# Arduino-Pro-Mini.net
KiCad netlist of a schematic drawn in EAGLE
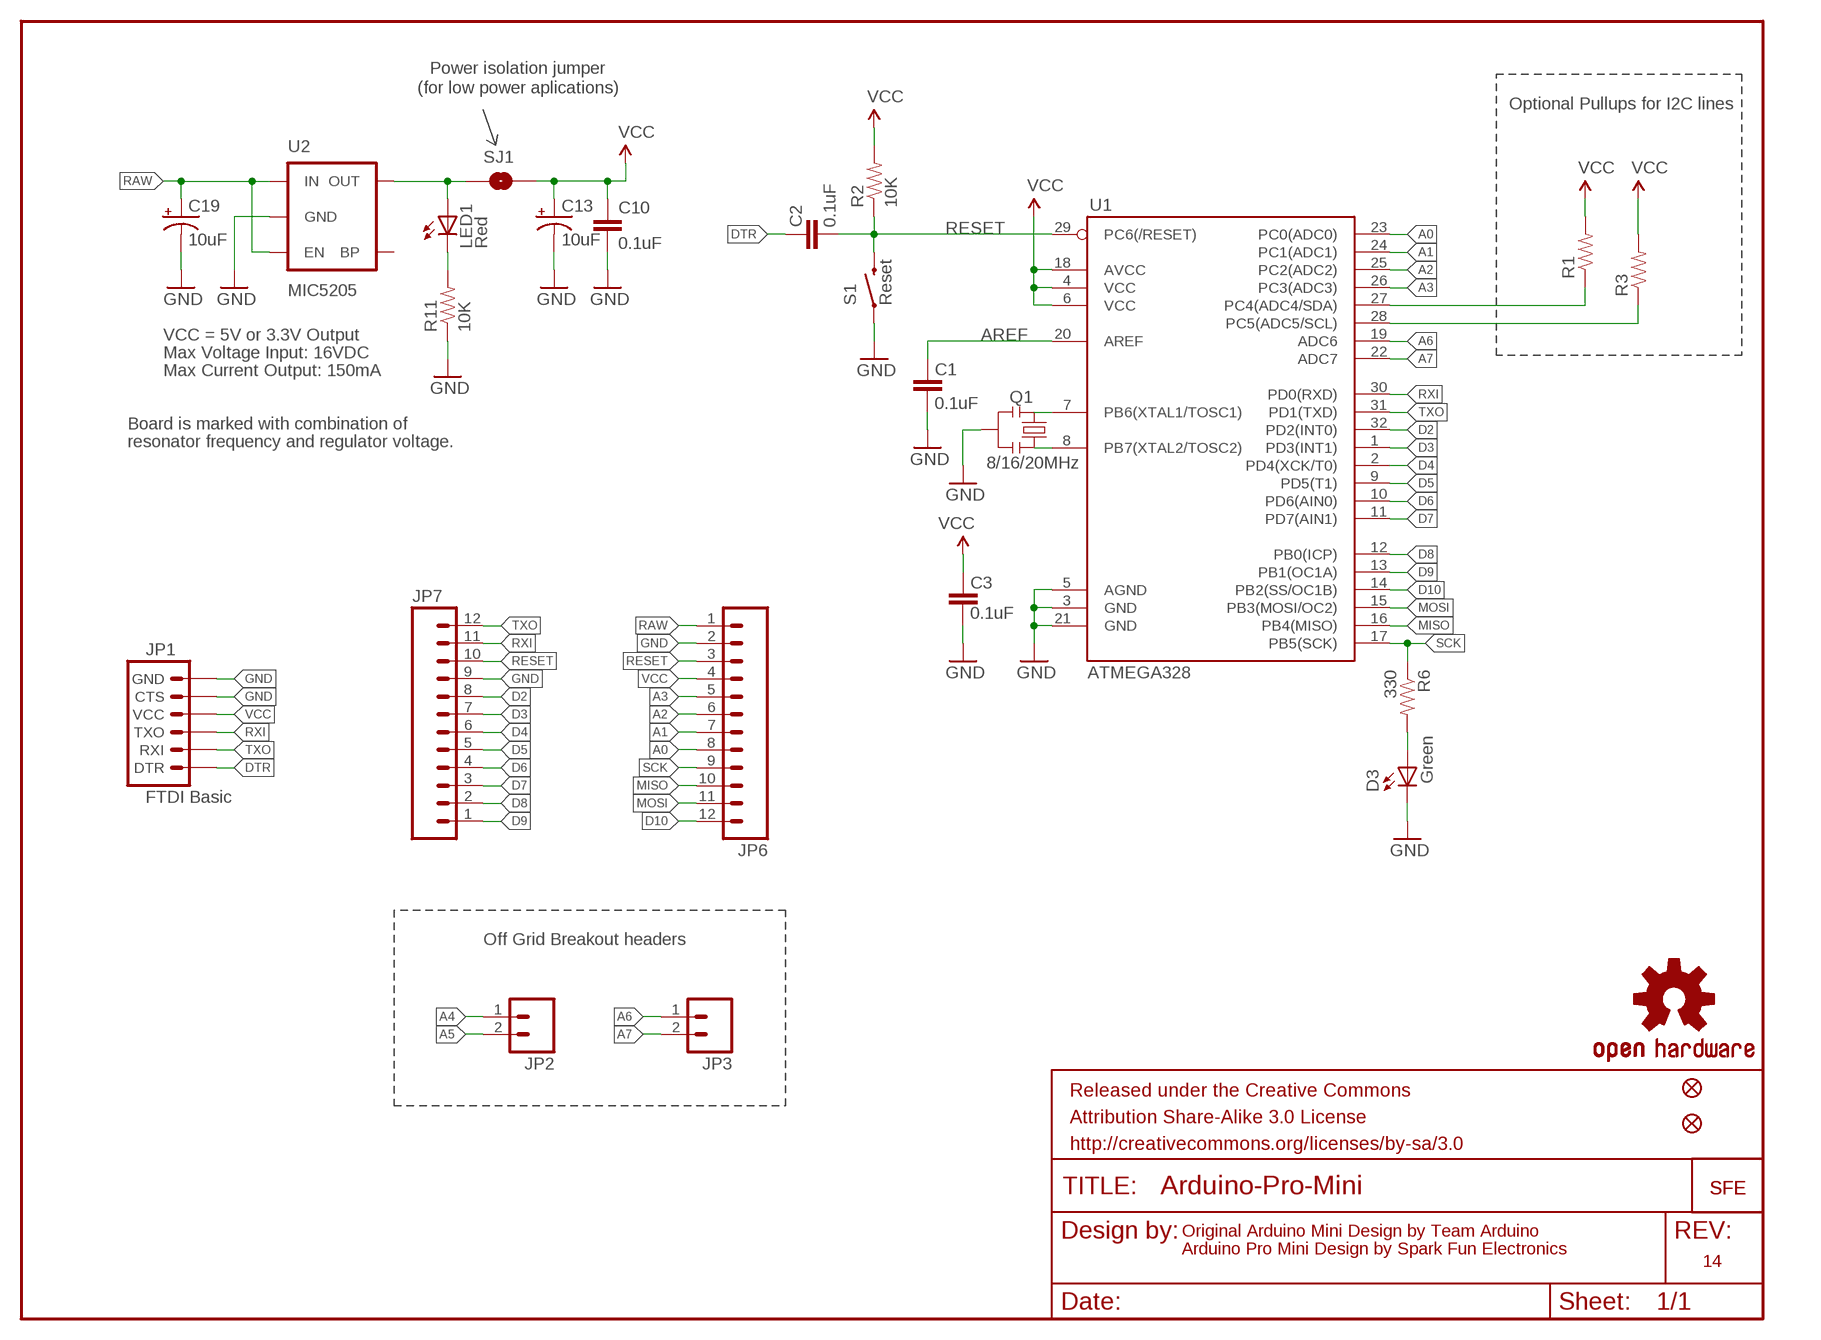
[diagram p0: schematic, sheet 1]

(export (version "E")
  (design (tool "Eeschema 10.0.6"))
  (components
    (comp (ref "C1")
      (value "0.1uF")
      (footprint "eagle-import:0603-CAP")
      (libsource (lib "eagle-import") (part "CAP0603-CAP"))
    )
    (comp (ref "C2")
      (value "0.1uF")
      (footprint "eagle-import:0603-CAP")
      (libsource (lib "eagle-import") (part "CAP0603-CAP"))
    )
    (comp (ref "C3")
      (value "0.1uF")
      (footprint "eagle-import:0603-CAP")
      (libsource (lib "eagle-import") (part "CAP0603-CAP"))
    )
    (comp (ref "C10")
      (value "0.1uF")
      (footprint "eagle-import:0603-CAP")
      (libsource (lib "eagle-import") (part "CAP0603-CAP"))
    )
    (comp (ref "C13")
      (value "10uF")
      (footprint "eagle-import:EIA3216")
      (libsource (lib "eagle-import") (part "CAP_POL1206"))
    )
    (comp (ref "C19")
      (value "10uF")
      (footprint "eagle-import:EIA3216")
      (libsource (lib "eagle-import") (part "CAP_POL1206"))
    )
    (comp (ref "D3")
      (value "Green")
      (footprint "eagle-import:LED-0603")
      (libsource (lib "eagle-import") (part "LED0603"))
    )
    (comp (ref "FRAME1")
      (value "FRAME-LETTER")
      (footprint "eagle-import:CREATIVE_COMMONS")
      (libsource (lib "eagle-import") (part "FRAME-LETTER"))
    )
    (comp (ref "JP1")
      (value "FTDI Basic")
      (footprint "eagle-import:1X06")
      (libsource (lib "eagle-import") (part "ARDUINO_SERIAL_PROGRAMPTH"))
    )
    (comp (ref "JP2")
      (value "M02PTH")
      (footprint "eagle-import:1X02")
      (libsource (lib "eagle-import") (part "M02PTH"))
    )
    (comp (ref "JP3")
      (value "M02PTH")
      (footprint "eagle-import:1X02")
      (libsource (lib "eagle-import") (part "M02PTH"))
    )
    (comp (ref "JP5")
      (value "FIDUCIALUFIDUCIAL")
      (footprint "eagle-import:MICRO-FIDUCIAL")
      (libsource (lib "eagle-import") (part "FIDUCIALUFIDUCIAL"))
    )
    (comp (ref "JP6")
      (value "M12PTH")
      (footprint "eagle-import:1X12")
      (libsource (lib "eagle-import") (part "M12PTH"))
    )
    (comp (ref "JP7")
      (value "M12PTH")
      (footprint "eagle-import:1X12")
      (libsource (lib "eagle-import") (part "M12PTH"))
    )
    (comp (ref "JP8")
      (value "FIDUCIALUFIDUCIAL")
      (footprint "eagle-import:MICRO-FIDUCIAL")
      (libsource (lib "eagle-import") (part "FIDUCIALUFIDUCIAL"))
    )
    (comp (ref "LED1")
      (value "Red")
      (footprint "eagle-import:LED-0603")
      (libsource (lib "eagle-import") (part "LED0603"))
    )
    (comp (ref "Q1")
      (value "8/16/20MHz")
      (footprint "eagle-import:RESONATOR-SMD-1_1")
      (libsource (lib "eagle-import") (part "RESONATOR1{colon}1"))
    )
    (comp (ref "R1")
      (value "RESISTOR0603-RES")
      (footprint "eagle-import:0603-RES")
      (libsource (lib "eagle-import") (part "RESISTOR0603-RES"))
    )
    (comp (ref "R2")
      (value "10K")
      (footprint "eagle-import:0603-RES")
      (libsource (lib "eagle-import") (part "RESISTOR0603-RES"))
    )
    (comp (ref "R3")
      (value "RESISTOR0603-RES")
      (footprint "eagle-import:0603-RES")
      (libsource (lib "eagle-import") (part "RESISTOR0603-RES"))
    )
    (comp (ref "R6")
      (value "330")
      (footprint "eagle-import:0603-RES")
      (libsource (lib "eagle-import") (part "RESISTOR0603-RES"))
    )
    (comp (ref "R11")
      (value "10K")
      (footprint "eagle-import:0603-RES")
      (libsource (lib "eagle-import") (part "RESISTOR0603-RES"))
    )
    (comp (ref "S1")
      (value "Reset")
      (footprint "eagle-import:TACTILE-SWITCH-SMD-ALT01")
      (libsource (lib "eagle-import") (part "SWITCH-MOMENTARY-2SMD-ALT01"))
    )
    (comp (ref "SJ1")
      (value "SOLDERJUMPERNC")
      (footprint "eagle-import:SJ_2S")
      (libsource (lib "eagle-import") (part "SOLDERJUMPERNC"))
    )
    (comp (ref "U$1")
      (value "LOGO-SFESK")
      (footprint "eagle-import:SFE-LOGO-FLAME")
      (libsource (lib "eagle-import") (part "LOGO-SFESK"))
    )
    (comp (ref "U$3")
      (value "OSHW-LOGOS")
      (footprint "eagle-import:OSHW-LOGO-S")
      (libsource (lib "eagle-import") (part "OSHW-LOGOS"))
    )
    (comp (ref "U$11")
      (value "LOGO-SFENEW")
      (footprint "eagle-import:SFE-NEW-WEBLOGO")
      (libsource (lib "eagle-import") (part "LOGO-SFENEW"))
    )
    (comp (ref "U1")
      (value "ATMEGA328")
      (footprint "eagle-import:TQFP32-08")
      (libsource (lib "eagle-import") (part "ATMEGA168"))
    )
    (comp (ref "U2")
      (value "MIC5205")
      (footprint "eagle-import:SOT23-5")
      (libsource (lib "eagle-import") (part "V_REG_LDOSMD"))
    )
  )
  (nets
    (net (code "1") (name "/AREF") (class "Default")
      (node (ref "C1") (pin "2") (pinfunction "2_2") (pintype "passive"))
      (node (ref "U1") (pin "20") (pinfunction "AREF_20") (pintype "bidirectional"))
    )
    (net (code "2") (name "A0") (class "Default")
      (node (ref "JP6") (pin "8") (pinfunction "8_8") (pintype "passive"))
      (node (ref "U1") (pin "23") (pinfunction "PC0(ADC0)_23") (pintype "bidirectional"))
    )
    (net (code "3") (name "A1") (class "Default")
      (node (ref "JP6") (pin "7") (pinfunction "7_7") (pintype "passive"))
      (node (ref "U1") (pin "24") (pinfunction "PC1(ADC1)_24") (pintype "bidirectional"))
    )
    (net (code "4") (name "A2") (class "Default")
      (node (ref "JP6") (pin "6") (pinfunction "6_6") (pintype "passive"))
      (node (ref "U1") (pin "25") (pinfunction "PC2(ADC2)_25") (pintype "bidirectional"))
    )
    (net (code "5") (name "A3") (class "Default")
      (node (ref "JP6") (pin "5") (pinfunction "5_5") (pintype "passive"))
      (node (ref "U1") (pin "26") (pinfunction "PC3(ADC3)_26") (pintype "bidirectional"))
    )
    (net (code "6") (name "A4") (class "Default")
      (node (ref "JP2") (pin "1") (pinfunction "1_1") (pintype "passive"))
      (node (ref "R1") (pin "1") (pinfunction "1_1") (pintype "passive"))
      (node (ref "U1") (pin "27") (pinfunction "PC4(ADC4/SDA)_27") (pintype "bidirectional"))
    )
    (net (code "7") (name "A5") (class "Default")
      (node (ref "JP2") (pin "2") (pinfunction "2_2") (pintype "passive"))
      (node (ref "R3") (pin "1") (pinfunction "1_1") (pintype "passive"))
      (node (ref "U1") (pin "28") (pinfunction "PC5(ADC5/SCL)_28") (pintype "bidirectional"))
    )
    (net (code "8") (name "A6") (class "Default")
      (node (ref "JP3") (pin "1") (pinfunction "1_1") (pintype "passive"))
      (node (ref "U1") (pin "19") (pinfunction "ADC6_19") (pintype "bidirectional"))
    )
    (net (code "9") (name "A7") (class "Default")
      (node (ref "JP3") (pin "2") (pinfunction "2_2") (pintype "passive"))
      (node (ref "U1") (pin "22") (pinfunction "ADC7_22") (pintype "bidirectional"))
    )
    (net (code "10") (name "D2") (class "Default")
      (node (ref "JP7") (pin "8") (pinfunction "8_8") (pintype "passive"))
      (node (ref "U1") (pin "32") (pinfunction "PD2(INT0)_32") (pintype "bidirectional"))
    )
    (net (code "11") (name "D3") (class "Default")
      (node (ref "JP7") (pin "7") (pinfunction "7_7") (pintype "passive"))
      (node (ref "U1") (pin "1") (pinfunction "PD3(INT1)_1") (pintype "bidirectional"))
    )
    (net (code "12") (name "D4") (class "Default")
      (node (ref "JP7") (pin "6") (pinfunction "6_6") (pintype "passive"))
      (node (ref "U1") (pin "2") (pinfunction "PD4(XCK/T0)_2") (pintype "bidirectional"))
    )
    (net (code "13") (name "D5") (class "Default")
      (node (ref "JP7") (pin "5") (pinfunction "5_5") (pintype "passive"))
      (node (ref "U1") (pin "9") (pinfunction "PD5(T1)_9") (pintype "bidirectional"))
    )
    (net (code "14") (name "D6") (class "Default")
      (node (ref "JP7") (pin "4") (pinfunction "4_4") (pintype "passive"))
      (node (ref "U1") (pin "10") (pinfunction "PD6(AIN0)_10") (pintype "bidirectional"))
    )
    (net (code "15") (name "D7") (class "Default")
      (node (ref "JP7") (pin "3") (pinfunction "3_3") (pintype "passive"))
      (node (ref "U1") (pin "11") (pinfunction "PD7(AIN1)_11") (pintype "bidirectional"))
    )
    (net (code "16") (name "D8") (class "Default")
      (node (ref "JP7") (pin "2") (pinfunction "2_2") (pintype "passive"))
      (node (ref "U1") (pin "12") (pinfunction "PB0(ICP)_12") (pintype "bidirectional"))
    )
    (net (code "17") (name "D9") (class "Default")
      (node (ref "JP7") (pin "1") (pinfunction "1_1") (pintype "passive"))
      (node (ref "U1") (pin "13") (pinfunction "PB1(OC1A)_13") (pintype "bidirectional"))
    )
    (net (code "18") (name "D10") (class "Default")
      (node (ref "JP6") (pin "12") (pinfunction "12_12") (pintype "passive"))
      (node (ref "U1") (pin "14") (pinfunction "PB2(SS/OC1B)_14") (pintype "bidirectional"))
    )
    (net (code "19") (name "DTR") (class "Default")
      (node (ref "C2") (pin "2") (pinfunction "2_2") (pintype "passive"))
      (node (ref "JP1") (pin "1") (pinfunction "DTR_1") (pintype "passive"))
    )
    (net (code "20") (name "GND") (class "Default")
      (node (ref "C1") (pin "1") (pinfunction "1_1") (pintype "passive"))
      (node (ref "C10") (pin "2") (pinfunction "2_2") (pintype "passive"))
      (node (ref "C13") (pin "C") (pinfunction "-_C") (pintype "passive"))
      (node (ref "C19") (pin "C") (pinfunction "-_C") (pintype "passive"))
      (node (ref "C3") (pin "1") (pinfunction "1_1") (pintype "passive"))
      (node (ref "D3") (pin "C") (pinfunction "C_C") (pintype "passive"))
      (node (ref "JP1") (pin "5") (pinfunction "CTS_5") (pintype "passive"))
      (node (ref "JP1") (pin "6") (pinfunction "GND_6") (pintype "passive"))
      (node (ref "JP6") (pin "2") (pinfunction "2_2") (pintype "passive"))
      (node (ref "JP7") (pin "9") (pinfunction "9_9") (pintype "passive"))
      (node (ref "Q1") (pin "2") (pinfunction "2_2") (pintype "passive"))
      (node (ref "R11") (pin "1") (pinfunction "1_1") (pintype "passive"))
      (node (ref "S1") (pin "1") (pinfunction "1_1") (pintype "passive"))
      (node (ref "S1") (pin "2") (pinfunction "1_2") (pintype "passive"))
      (node (ref "U1") (pin "21") (pinfunction "GND_21") (pintype "bidirectional"))
      (node (ref "U1") (pin "3") (pinfunction "GND_3") (pintype "bidirectional"))
      (node (ref "U1") (pin "5") (pinfunction "AGND_5") (pintype "bidirectional"))
      (node (ref "U2") (pin "2") (pinfunction "GND_2") (pintype "input"))
    )
    (net (code "21") (name "MISO") (class "Default")
      (node (ref "JP6") (pin "10") (pinfunction "10_10") (pintype "passive"))
      (node (ref "U1") (pin "16") (pinfunction "PB4(MISO)_16") (pintype "bidirectional"))
    )
    (net (code "22") (name "MOSI") (class "Default")
      (node (ref "JP6") (pin "11") (pinfunction "11_11") (pintype "passive"))
      (node (ref "U1") (pin "15") (pinfunction "PB3(MOSI/OC2)_15") (pintype "bidirectional"))
    )
    (net (code "23") (name "Net-(D3-PadA)") (class "Default")
      (node (ref "D3") (pin "A") (pinfunction "A_A") (pintype "passive"))
      (node (ref "R6") (pin "2") (pinfunction "2_2") (pintype "passive"))
    )
    (net (code "24") (name "Net-(LED1-PadC)") (class "Default")
      (node (ref "LED1") (pin "C") (pinfunction "C_C") (pintype "passive"))
      (node (ref "R11") (pin "2") (pinfunction "2_2") (pintype "passive"))
    )
    (net (code "25") (name "Net-(U1-PB6(XTAL1{slash}TOSC1))") (class "Default")
      (node (ref "Q1") (pin "1") (pinfunction "1_1") (pintype "passive"))
      (node (ref "U1") (pin "7") (pinfunction "PB6(XTAL1/TOSC1)_7") (pintype "bidirectional"))
    )
    (net (code "26") (name "Net-(U1-PB7(XTAL2{slash}TOSC2))") (class "Default")
      (node (ref "Q1") (pin "3") (pinfunction "3_3") (pintype "passive"))
      (node (ref "U1") (pin "8") (pinfunction "PB7(XTAL2/TOSC2)_8") (pintype "bidirectional"))
    )
    (net (code "27") (name "Net-(U2-OUT)") (class "Default")
      (node (ref "LED1") (pin "A") (pinfunction "A_A") (pintype "passive"))
      (node (ref "SJ1") (pin "1") (pinfunction "1_1") (pintype "passive"))
      (node (ref "U2") (pin "5") (pinfunction "OUT_5") (pintype "passive"))
    )
    (net (code "28") (name "RAW") (class "Default")
      (node (ref "C19") (pin "A") (pinfunction "+_A") (pintype "passive"))
      (node (ref "JP6") (pin "1") (pinfunction "1_1") (pintype "passive"))
      (node (ref "U2") (pin "1") (pinfunction "IN_1") (pintype "input"))
      (node (ref "U2") (pin "3") (pinfunction "EN_3") (pintype "input"))
    )
    (net (code "29") (name "RESET") (class "Default")
      (node (ref "C2") (pin "1") (pinfunction "1_1") (pintype "passive"))
      (node (ref "JP6") (pin "3") (pinfunction "3_3") (pintype "passive"))
      (node (ref "JP7") (pin "10") (pinfunction "10_10") (pintype "passive"))
      (node (ref "R2") (pin "1") (pinfunction "1_1") (pintype "passive"))
      (node (ref "S1") (pin "3") (pinfunction "2_3") (pintype "passive"))
      (node (ref "S1") (pin "4") (pinfunction "2_4") (pintype "passive"))
      (node (ref "U1") (pin "29") (pinfunction "PC6(/RESET)_29") (pintype "bidirectional"))
    )
    (net (code "30") (name "RXI") (class "Default")
      (node (ref "JP1") (pin "3") (pinfunction "TXO_3") (pintype "passive"))
      (node (ref "JP7") (pin "11") (pinfunction "11_11") (pintype "passive"))
      (node (ref "U1") (pin "30") (pinfunction "PD0(RXD)_30") (pintype "bidirectional"))
    )
    (net (code "31") (name "SCK") (class "Default")
      (node (ref "JP6") (pin "9") (pinfunction "9_9") (pintype "passive"))
      (node (ref "R6") (pin "1") (pinfunction "1_1") (pintype "passive"))
      (node (ref "U1") (pin "17") (pinfunction "PB5(SCK)_17") (pintype "bidirectional"))
    )
    (net (code "32") (name "TXO") (class "Default")
      (node (ref "JP1") (pin "2") (pinfunction "RXI_2") (pintype "passive"))
      (node (ref "JP7") (pin "12") (pinfunction "12_12") (pintype "passive"))
      (node (ref "U1") (pin "31") (pinfunction "PD1(TXD)_31") (pintype "bidirectional"))
    )
    (net (code "33") (name "VCC") (class "Default")
      (node (ref "C10") (pin "1") (pinfunction "1_1") (pintype "passive"))
      (node (ref "C13") (pin "A") (pinfunction "+_A") (pintype "passive"))
      (node (ref "C3") (pin "2") (pinfunction "2_2") (pintype "passive"))
      (node (ref "JP1") (pin "4") (pinfunction "VCC_4") (pintype "passive"))
      (node (ref "JP6") (pin "4") (pinfunction "4_4") (pintype "passive"))
      (node (ref "R1") (pin "2") (pinfunction "2_2") (pintype "passive"))
      (node (ref "R2") (pin "2") (pinfunction "2_2") (pintype "passive"))
      (node (ref "R3") (pin "2") (pinfunction "2_2") (pintype "passive"))
      (node (ref "SJ1") (pin "2") (pinfunction "2_2") (pintype "passive"))
      (node (ref "U1") (pin "18") (pinfunction "AVCC_18") (pintype "bidirectional"))
      (node (ref "U1") (pin "4") (pinfunction "VCC_4") (pintype "bidirectional"))
      (node (ref "U1") (pin "6") (pinfunction "VCC_6") (pintype "bidirectional"))
    )
    (net (code "34") (name "unconnected-(U2-BP-Pad4)") (class "Default")
      (node (ref "U2") (pin "4") (pinfunction "BP_4") (pintype "input"))
    )
  )
)
